# EMG_EEG_PreAmp_Alpha1c.net
KiCad netlist of a schematic drawn in EAGLE
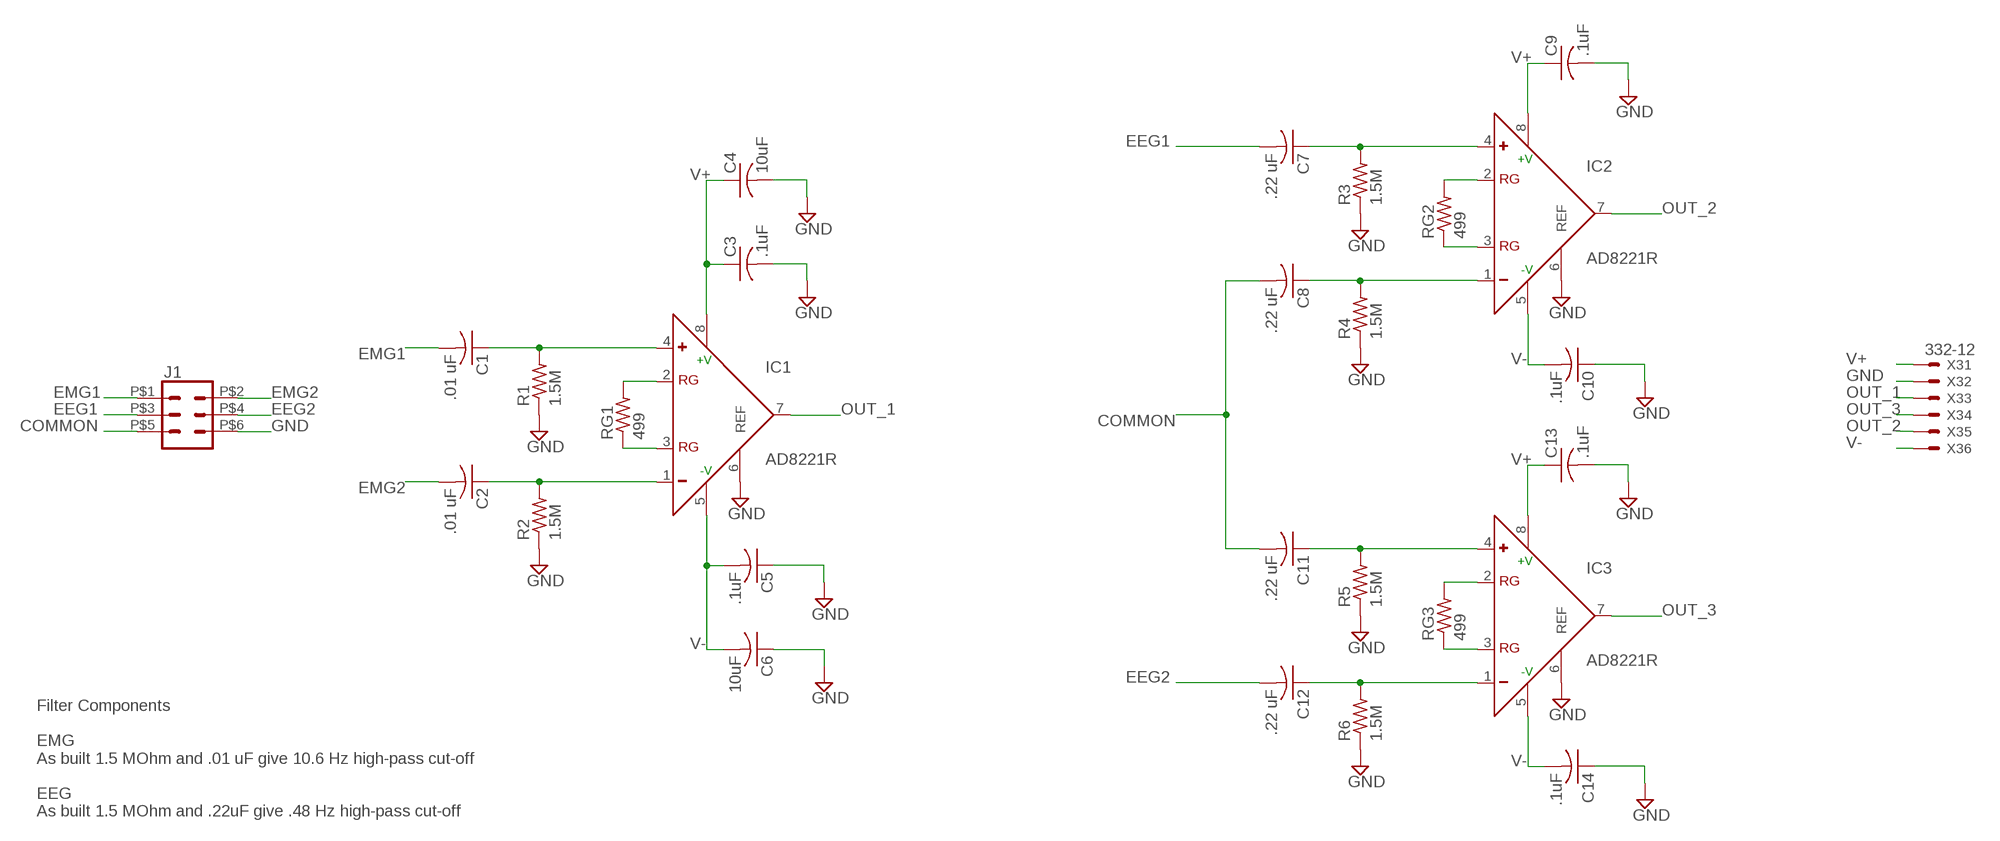
[diagram p0: schematic, sheet 1]

(export (version "E")
  (design (tool "Eeschema 10.0.6"))
  (components
    (comp (ref "C1")
      (value ".01 uF")
      (footprint "eagle-import:C0805K")
      (libsource (lib "eagle-import") (part "C-USC0805K"))
    )
    (comp (ref "C2")
      (value ".01 uF")
      (footprint "eagle-import:C0805K")
      (libsource (lib "eagle-import") (part "C-USC0805K"))
    )
    (comp (ref "C3")
      (value ".1uF")
      (footprint "eagle-import:C0805K")
      (libsource (lib "eagle-import") (part "C-USC0805K"))
    )
    (comp (ref "C4")
      (value "10uF")
      (footprint "eagle-import:C0805K")
      (libsource (lib "eagle-import") (part "C-USC0805K"))
    )
    (comp (ref "C5")
      (value ".1uF")
      (footprint "eagle-import:C0805K")
      (libsource (lib "eagle-import") (part "C-USC0805K"))
    )
    (comp (ref "C6")
      (value "10uF")
      (footprint "eagle-import:C0805K")
      (libsource (lib "eagle-import") (part "C-USC0805K"))
    )
    (comp (ref "C7")
      (value ".22 uF")
      (footprint "eagle-import:C0805K")
      (libsource (lib "eagle-import") (part "C-USC0805K"))
    )
    (comp (ref "C8")
      (value ".22 uF")
      (footprint "eagle-import:C0805K")
      (libsource (lib "eagle-import") (part "C-USC0805K"))
    )
    (comp (ref "C9")
      (value ".1uF")
      (footprint "eagle-import:C0805K")
      (libsource (lib "eagle-import") (part "C-USC0805K"))
    )
    (comp (ref "C10")
      (value ".1uF")
      (footprint "eagle-import:C0805K")
      (libsource (lib "eagle-import") (part "C-USC0805K"))
    )
    (comp (ref "C11")
      (value ".22 uF")
      (footprint "eagle-import:C0805K")
      (libsource (lib "eagle-import") (part "C-USC0805K"))
    )
    (comp (ref "C12")
      (value ".22 uF")
      (footprint "eagle-import:C0805K")
      (libsource (lib "eagle-import") (part "C-USC0805K"))
    )
    (comp (ref "C13")
      (value ".1uF")
      (footprint "eagle-import:C0805K")
      (libsource (lib "eagle-import") (part "C-USC0805K"))
    )
    (comp (ref "C14")
      (value ".1uF")
      (footprint "eagle-import:C0805K")
      (libsource (lib "eagle-import") (part "C-USC0805K"))
    )
    (comp (ref "IC1")
      (value "AD8221R")
      (footprint "eagle-import:SO8")
      (fields (field (name "MPN") "AD620AR"))
      (libsource (lib "eagle-import") (part "AD8221R"))
    )
    (comp (ref "IC2")
      (value "AD8221R")
      (footprint "eagle-import:SO8")
      (fields (field (name "MPN") "AD620AR"))
      (libsource (lib "eagle-import") (part "AD8221R"))
    )
    (comp (ref "IC3")
      (value "AD8221R")
      (footprint "eagle-import:SO8")
      (fields (field (name "MPN") "AD620AR"))
      (libsource (lib "eagle-import") (part "AD8221R"))
    )
    (comp (ref "J1")
      (value "2X3MILL-MAX")
      (footprint "eagle-import:2X3_MILL-MAX_853")
      (libsource (lib "eagle-import") (part "2X3MILL-MAX"))
    )
    (comp (ref "R1")
      (value "1.5M")
      (footprint "eagle-import:R0805")
      (libsource (lib "eagle-import") (part "R-US_R0805"))
    )
    (comp (ref "R2")
      (value "1.5M")
      (footprint "eagle-import:R0805")
      (libsource (lib "eagle-import") (part "R-US_R0805"))
    )
    (comp (ref "R3")
      (value "1.5M")
      (footprint "eagle-import:R0805")
      (libsource (lib "eagle-import") (part "R-US_R0805"))
    )
    (comp (ref "R4")
      (value "1.5M")
      (footprint "eagle-import:R0805")
      (libsource (lib "eagle-import") (part "R-US_R0805"))
    )
    (comp (ref "R5")
      (value "1.5M")
      (footprint "eagle-import:R0805")
      (libsource (lib "eagle-import") (part "R-US_R0805"))
    )
    (comp (ref "R6")
      (value "1.5M")
      (footprint "eagle-import:R0805")
      (libsource (lib "eagle-import") (part "R-US_R0805"))
    )
    (comp (ref "RG1")
      (value "499")
      (footprint "eagle-import:R0805")
      (libsource (lib "eagle-import") (part "R-US_R0805"))
    )
    (comp (ref "RG2")
      (value "499")
      (footprint "eagle-import:R0805")
      (libsource (lib "eagle-import") (part "R-US_R0805"))
    )
    (comp (ref "RG3")
      (value "499")
      (footprint "eagle-import:R0805")
      (libsource (lib "eagle-import") (part "R-US_R0805"))
    )
    (comp (ref "X3")
      (value "332-12")
      (footprint "eagle-import:1X6_WITH_STRAIN_RELIEF")
      (libsource (lib "eagle-import") (part "332-12"))
    )
  )
  (nets
    (net (code "1") (name "/COMMON") (class "Default")
      (node (ref "C11") (pin "2") (pinfunction "2_2") (pintype "passive"))
      (node (ref "C8") (pin "2") (pinfunction "2_2") (pintype "passive"))
      (node (ref "J1") (pin "P$5") (pinfunction "5_P$5") (pintype "bidirectional"))
    )
    (net (code "2") (name "/EEG1") (class "Default")
      (node (ref "C7") (pin "2") (pinfunction "2_2") (pintype "passive"))
      (node (ref "J1") (pin "P$3") (pinfunction "3_P$3") (pintype "bidirectional"))
    )
    (net (code "3") (name "/EEG2") (class "Default")
      (node (ref "C12") (pin "2") (pinfunction "2_2") (pintype "passive"))
      (node (ref "J1") (pin "P$4") (pinfunction "4_P$4") (pintype "bidirectional"))
    )
    (net (code "4") (name "/EMG1") (class "Default")
      (node (ref "C1") (pin "2") (pinfunction "2_2") (pintype "passive"))
      (node (ref "J1") (pin "P$1") (pinfunction "1_P$1") (pintype "bidirectional"))
    )
    (net (code "5") (name "/EMG2") (class "Default")
      (node (ref "C2") (pin "2") (pinfunction "2_2") (pintype "passive"))
      (node (ref "J1") (pin "P$2") (pinfunction "2_P$2") (pintype "bidirectional"))
    )
    (net (code "6") (name "/OUT_1") (class "Default")
      (node (ref "IC1") (pin "7") (pinfunction "OUT_7") (pintype "output"))
      (node (ref "X3") (pin "3") (pinfunction "S_3") (pintype "passive"))
    )
    (net (code "7") (name "/OUT_2") (class "Default")
      (node (ref "IC2") (pin "7") (pinfunction "OUT_7") (pintype "output"))
      (node (ref "X3") (pin "5") (pinfunction "S_5") (pintype "passive"))
    )
    (net (code "8") (name "/OUT_3") (class "Default")
      (node (ref "IC3") (pin "7") (pinfunction "OUT_7") (pintype "output"))
      (node (ref "X3") (pin "4") (pinfunction "S_4") (pintype "passive"))
    )
    (net (code "9") (name "/V+") (class "Default")
      (node (ref "C13") (pin "1") (pinfunction "1_1") (pintype "passive"))
      (node (ref "C3") (pin "1") (pinfunction "1_1") (pintype "passive"))
      (node (ref "C4") (pin "1") (pinfunction "1_1") (pintype "passive"))
      (node (ref "C9") (pin "1") (pinfunction "1_1") (pintype "passive"))
      (node (ref "IC1") (pin "8") (pinfunction "+V_8") (pintype "power_in"))
      (node (ref "IC2") (pin "8") (pinfunction "+V_8") (pintype "power_in"))
      (node (ref "IC3") (pin "8") (pinfunction "+V_8") (pintype "power_in"))
      (node (ref "X3") (pin "1") (pinfunction "S_1") (pintype "passive"))
    )
    (net (code "10") (name "/V-") (class "Default")
      (node (ref "C10") (pin "2") (pinfunction "2_2") (pintype "passive"))
      (node (ref "C14") (pin "2") (pinfunction "2_2") (pintype "passive"))
      (node (ref "C5") (pin "2") (pinfunction "2_2") (pintype "passive"))
      (node (ref "C6") (pin "2") (pinfunction "2_2") (pintype "passive"))
      (node (ref "IC1") (pin "5") (pinfunction "-V_5") (pintype "power_in"))
      (node (ref "IC2") (pin "5") (pinfunction "-V_5") (pintype "power_in"))
      (node (ref "IC3") (pin "5") (pinfunction "-V_5") (pintype "power_in"))
      (node (ref "X3") (pin "6") (pinfunction "S_6") (pintype "passive"))
    )
    (net (code "11") (name "GND") (class "Default")
      (node (ref "C10") (pin "1") (pinfunction "1_1") (pintype "passive"))
      (node (ref "C13") (pin "2") (pinfunction "2_2") (pintype "passive"))
      (node (ref "C14") (pin "1") (pinfunction "1_1") (pintype "passive"))
      (node (ref "C3") (pin "2") (pinfunction "2_2") (pintype "passive"))
      (node (ref "C4") (pin "2") (pinfunction "2_2") (pintype "passive"))
      (node (ref "C5") (pin "1") (pinfunction "1_1") (pintype "passive"))
      (node (ref "C6") (pin "1") (pinfunction "1_1") (pintype "passive"))
      (node (ref "C9") (pin "2") (pinfunction "2_2") (pintype "passive"))
      (node (ref "IC1") (pin "6") (pinfunction "REF_6") (pintype "passive"))
      (node (ref "IC2") (pin "6") (pinfunction "REF_6") (pintype "passive"))
      (node (ref "IC3") (pin "6") (pinfunction "REF_6") (pintype "passive"))
      (node (ref "J1") (pin "P$6") (pinfunction "6_P$6") (pintype "bidirectional"))
      (node (ref "R1") (pin "1") (pinfunction "1_1") (pintype "passive"))
      (node (ref "R2") (pin "1") (pinfunction "1_1") (pintype "passive"))
      (node (ref "R3") (pin "1") (pinfunction "1_1") (pintype "passive"))
      (node (ref "R4") (pin "1") (pinfunction "1_1") (pintype "passive"))
      (node (ref "R5") (pin "1") (pinfunction "1_1") (pintype "passive"))
      (node (ref "R6") (pin "1") (pinfunction "1_1") (pintype "passive"))
      (node (ref "X3") (pin "2") (pinfunction "S_2") (pintype "passive"))
    )
    (net (code "12") (name "Net-(IC1-+)") (class "Default")
      (node (ref "C1") (pin "1") (pinfunction "1_1") (pintype "passive"))
      (node (ref "IC1") (pin "4") (pinfunction "+_4") (pintype "input"))
      (node (ref "R1") (pin "2") (pinfunction "2_2") (pintype "passive"))
    )
    (net (code "13") (name "Net-(IC1--)") (class "Default")
      (node (ref "C2") (pin "1") (pinfunction "1_1") (pintype "passive"))
      (node (ref "IC1") (pin "1") (pinfunction "-_1") (pintype "input"))
      (node (ref "R2") (pin "2") (pinfunction "2_2") (pintype "passive"))
    )
    (net (code "14") (name "Net-(IC1-RG-Pad2)") (class "Default")
      (node (ref "IC1") (pin "2") (pinfunction "RG_2") (pintype "passive"))
      (node (ref "RG1") (pin "2") (pinfunction "2_2") (pintype "passive"))
    )
    (net (code "15") (name "Net-(IC1-RG-Pad3)") (class "Default")
      (node (ref "IC1") (pin "3") (pinfunction "RG_3") (pintype "passive"))
      (node (ref "RG1") (pin "1") (pinfunction "1_1") (pintype "passive"))
    )
    (net (code "16") (name "Net-(IC2-+)") (class "Default")
      (node (ref "C7") (pin "1") (pinfunction "1_1") (pintype "passive"))
      (node (ref "IC2") (pin "4") (pinfunction "+_4") (pintype "input"))
      (node (ref "R3") (pin "2") (pinfunction "2_2") (pintype "passive"))
    )
    (net (code "17") (name "Net-(IC2--)") (class "Default")
      (node (ref "C8") (pin "1") (pinfunction "1_1") (pintype "passive"))
      (node (ref "IC2") (pin "1") (pinfunction "-_1") (pintype "input"))
      (node (ref "R4") (pin "2") (pinfunction "2_2") (pintype "passive"))
    )
    (net (code "18") (name "Net-(IC2-RG-Pad2)") (class "Default")
      (node (ref "IC2") (pin "2") (pinfunction "RG_2") (pintype "passive"))
      (node (ref "RG2") (pin "2") (pinfunction "2_2") (pintype "passive"))
    )
    (net (code "19") (name "Net-(IC2-RG-Pad3)") (class "Default")
      (node (ref "IC2") (pin "3") (pinfunction "RG_3") (pintype "passive"))
      (node (ref "RG2") (pin "1") (pinfunction "1_1") (pintype "passive"))
    )
    (net (code "20") (name "Net-(IC3-+)") (class "Default")
      (node (ref "C11") (pin "1") (pinfunction "1_1") (pintype "passive"))
      (node (ref "IC3") (pin "4") (pinfunction "+_4") (pintype "input"))
      (node (ref "R5") (pin "2") (pinfunction "2_2") (pintype "passive"))
    )
    (net (code "21") (name "Net-(IC3--)") (class "Default")
      (node (ref "C12") (pin "1") (pinfunction "1_1") (pintype "passive"))
      (node (ref "IC3") (pin "1") (pinfunction "-_1") (pintype "input"))
      (node (ref "R6") (pin "2") (pinfunction "2_2") (pintype "passive"))
    )
    (net (code "22") (name "Net-(IC3-RG-Pad2)") (class "Default")
      (node (ref "IC3") (pin "2") (pinfunction "RG_2") (pintype "passive"))
      (node (ref "RG3") (pin "2") (pinfunction "2_2") (pintype "passive"))
    )
    (net (code "23") (name "Net-(IC3-RG-Pad3)") (class "Default")
      (node (ref "IC3") (pin "3") (pinfunction "RG_3") (pintype "passive"))
      (node (ref "RG3") (pin "1") (pinfunction "1_1") (pintype "passive"))
    )
  )
)
